# Western_Aero_2020.net
KiCad netlist of a schematic drawn in EAGLE
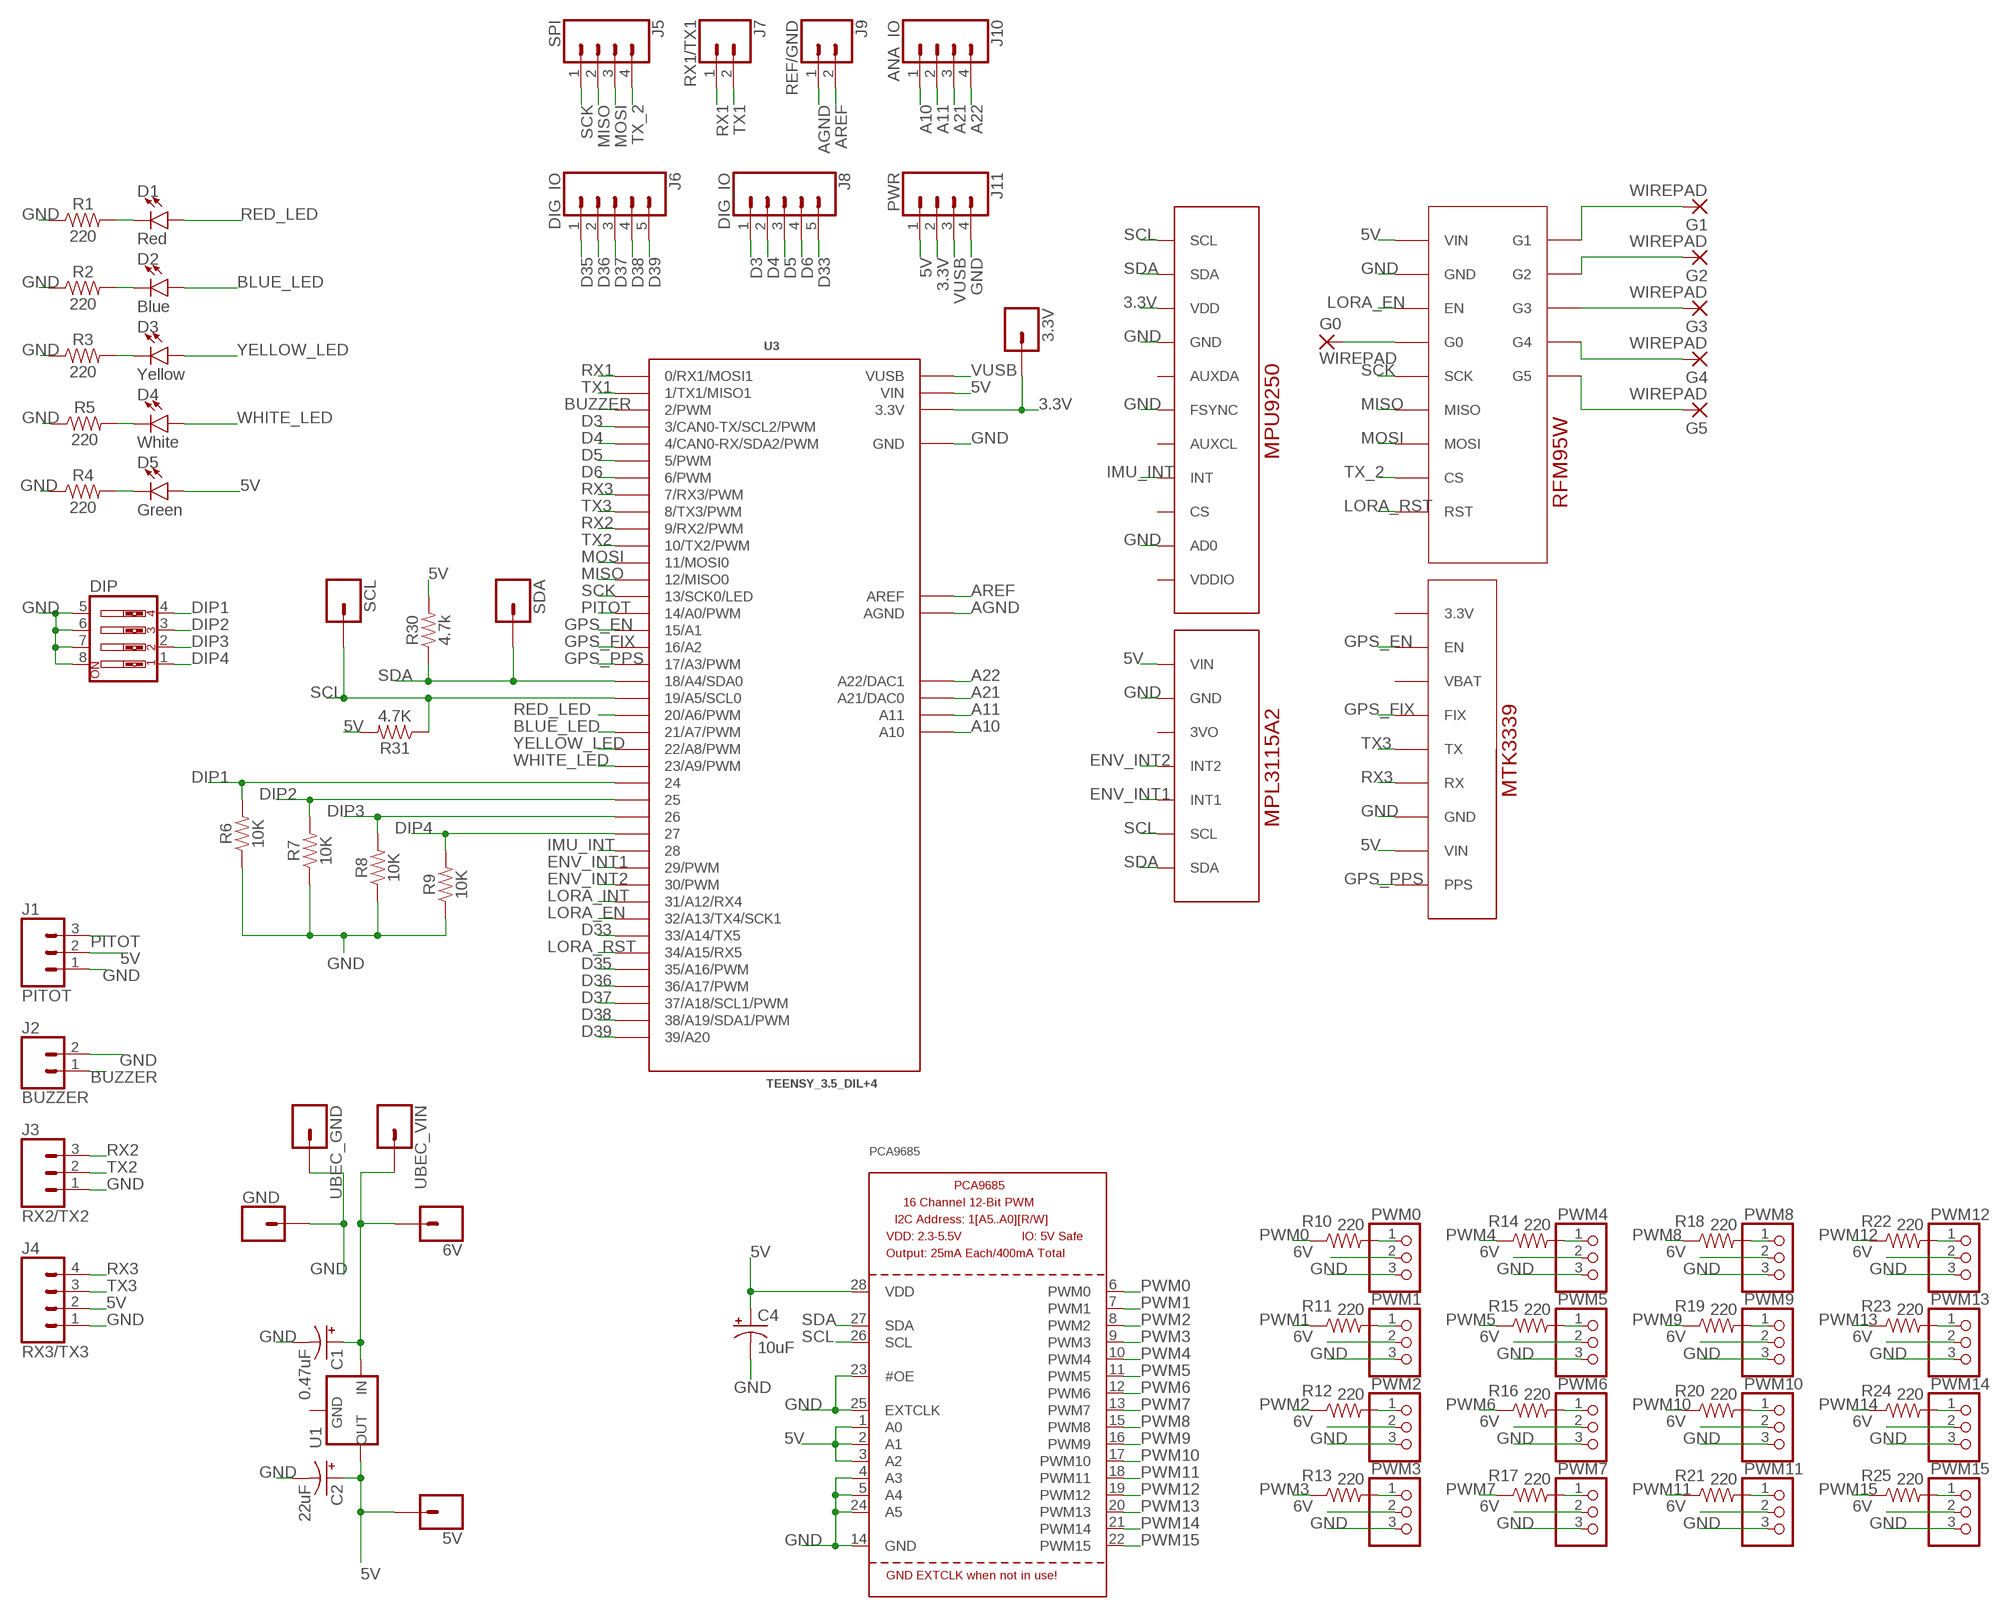
[diagram p0: schematic, sheet 1]

(export (version "E")
  (design (tool "Eeschema 10.0.6"))
  (components
    (comp (ref "3.3V")
      (value "CONN_01")
      (footprint "eagle-import:1X01")
      (libsource (lib "eagle-import") (part "CONN_01"))
    )
    (comp (ref "5V")
      (value "CONN_01")
      (footprint "eagle-import:1X01")
      (libsource (lib "eagle-import") (part "CONN_01"))
    )
    (comp (ref "6V")
      (value "CONN_01")
      (footprint "eagle-import:1X01")
      (libsource (lib "eagle-import") (part "CONN_01"))
    )
    (comp (ref "C1")
      (value "0.47uF")
      (footprint "eagle-import:CPOL-RADIAL-2.5MM-5MM")
      (libsource (lib "eagle-import") (part "10UF-POLAR-RADIAL-2.5MM-25V-20%"))
    )
    (comp (ref "C2")
      (value "22uF")
      (footprint "eagle-import:CPOL-RADIAL-2.5MM-5MM")
      (libsource (lib "eagle-import") (part "10UF-POLAR-RADIAL-2.5MM-25V-20%"))
    )
    (comp (ref "C4")
      (value "10uF")
      (footprint "eagle-import:CPOL-RADIAL-2.5MM-5MM")
      (libsource (lib "eagle-import") (part "10UF-POLAR-RADIAL-2.5MM-25V-20%"))
    )
    (comp (ref "D1")
      (value "Red")
      (footprint "eagle-import:LED_3MM")
      (libsource (lib "eagle-import") (part "LED3MM"))
    )
    (comp (ref "D2")
      (value "Blue")
      (footprint "eagle-import:LED_3MM")
      (libsource (lib "eagle-import") (part "LED3MM"))
    )
    (comp (ref "D3")
      (value "Yellow")
      (footprint "eagle-import:LED_3MM")
      (libsource (lib "eagle-import") (part "LED3MM"))
    )
    (comp (ref "D4")
      (value "White")
      (footprint "eagle-import:LED_3MM")
      (libsource (lib "eagle-import") (part "LED3MM"))
    )
    (comp (ref "D5")
      (value "Green")
      (footprint "eagle-import:LED_3MM")
      (libsource (lib "eagle-import") (part "LED3MM"))
    )
    (comp (ref "DIP")
      (value "SW_DIP-4")
      (footprint "eagle-import:EDG-04")
      (libsource (lib "eagle-import") (part "SW_DIP-4"))
    )
    (comp (ref "G0")
      (value "WIREPAD")
      (footprint "eagle-import:2,15_1,0")
      (libsource (lib "eagle-import") (part "WIREPAD2,15/1,0"))
    )
    (comp (ref "G1")
      (value "WIREPAD")
      (footprint "eagle-import:2,15_1,0")
      (libsource (lib "eagle-import") (part "WIREPAD2,15/1,0"))
    )
    (comp (ref "G2")
      (value "WIREPAD")
      (footprint "eagle-import:2,15_1,0")
      (libsource (lib "eagle-import") (part "WIREPAD2,15/1,0"))
    )
    (comp (ref "G3")
      (value "WIREPAD")
      (footprint "eagle-import:2,15_1,0")
      (libsource (lib "eagle-import") (part "WIREPAD2,15/1,0"))
    )
    (comp (ref "G4")
      (value "WIREPAD")
      (footprint "eagle-import:2,15_1,0")
      (libsource (lib "eagle-import") (part "WIREPAD2,15/1,0"))
    )
    (comp (ref "G5")
      (value "WIREPAD")
      (footprint "eagle-import:2,15_1,0")
      (libsource (lib "eagle-import") (part "WIREPAD2,15/1,0"))
    )
    (comp (ref "GND")
      (value "CONN_01")
      (footprint "eagle-import:1X01")
      (libsource (lib "eagle-import") (part "CONN_01"))
    )
    (comp (ref "J1")
      (value "PITOT")
      (footprint "eagle-import:1X03")
      (libsource (lib "eagle-import") (part "CONN_03"))
    )
    (comp (ref "J2")
      (value "BUZZER")
      (footprint "eagle-import:1X02")
      (libsource (lib "eagle-import") (part "CONN_02"))
    )
    (comp (ref "J3")
      (value "RX2/TX2")
      (footprint "eagle-import:1X03")
      (libsource (lib "eagle-import") (part "CONN_03"))
    )
    (comp (ref "J4")
      (value "RX3/TX3")
      (footprint "eagle-import:1X04")
      (libsource (lib "eagle-import") (part "CONN_04"))
    )
    (comp (ref "J5")
      (value "SPI")
      (footprint "eagle-import:1X04")
      (libsource (lib "eagle-import") (part "CONN_04"))
    )
    (comp (ref "J6")
      (value "DIG_IO")
      (footprint "eagle-import:1X05")
      (libsource (lib "eagle-import") (part "CONN_05"))
    )
    (comp (ref "J7")
      (value "RX1/TX1")
      (footprint "eagle-import:1X02")
      (libsource (lib "eagle-import") (part "CONN_02"))
    )
    (comp (ref "J8")
      (value "DIG_IO")
      (footprint "eagle-import:1X05")
      (libsource (lib "eagle-import") (part "CONN_05"))
    )
    (comp (ref "J9")
      (value "REF/GND")
      (footprint "eagle-import:1X02")
      (libsource (lib "eagle-import") (part "CONN_02"))
    )
    (comp (ref "J10")
      (value "ANA_IO")
      (footprint "eagle-import:1X04")
      (libsource (lib "eagle-import") (part "CONN_04"))
    )
    (comp (ref "J11")
      (value "PWR")
      (footprint "eagle-import:1X04")
      (libsource (lib "eagle-import") (part "CONN_04"))
    )
    (comp (ref "JP1")
      (value "PWM0")
      (footprint "eagle-import:1X03")
      (libsource (lib "eagle-import") (part "PINHD-1X3"))
    )
    (comp (ref "JP2")
      (value "PWM1")
      (footprint "eagle-import:1X03")
      (libsource (lib "eagle-import") (part "PINHD-1X3"))
    )
    (comp (ref "JP3")
      (value "PWM2")
      (footprint "eagle-import:1X03")
      (libsource (lib "eagle-import") (part "PINHD-1X3"))
    )
    (comp (ref "JP4")
      (value "PWM3")
      (footprint "eagle-import:1X03")
      (libsource (lib "eagle-import") (part "PINHD-1X3"))
    )
    (comp (ref "JP5")
      (value "PWM4")
      (footprint "eagle-import:1X03")
      (libsource (lib "eagle-import") (part "PINHD-1X3"))
    )
    (comp (ref "JP6")
      (value "PWM5")
      (footprint "eagle-import:1X03")
      (libsource (lib "eagle-import") (part "PINHD-1X3"))
    )
    (comp (ref "JP7")
      (value "PWM6")
      (footprint "eagle-import:1X03")
      (libsource (lib "eagle-import") (part "PINHD-1X3"))
    )
    (comp (ref "JP8")
      (value "PWM7")
      (footprint "eagle-import:1X03")
      (libsource (lib "eagle-import") (part "PINHD-1X3"))
    )
    (comp (ref "JP9")
      (value "PWM8")
      (footprint "eagle-import:1X03")
      (libsource (lib "eagle-import") (part "PINHD-1X3"))
    )
    (comp (ref "JP10")
      (value "PWM9")
      (footprint "eagle-import:1X03")
      (libsource (lib "eagle-import") (part "PINHD-1X3"))
    )
    (comp (ref "JP11")
      (value "PWM10")
      (footprint "eagle-import:1X03")
      (libsource (lib "eagle-import") (part "PINHD-1X3"))
    )
    (comp (ref "JP12")
      (value "PWM11")
      (footprint "eagle-import:1X03")
      (libsource (lib "eagle-import") (part "PINHD-1X3"))
    )
    (comp (ref "JP13")
      (value "PWM12")
      (footprint "eagle-import:1X03")
      (libsource (lib "eagle-import") (part "PINHD-1X3"))
    )
    (comp (ref "JP14")
      (value "PWM13")
      (footprint "eagle-import:1X03")
      (libsource (lib "eagle-import") (part "PINHD-1X3"))
    )
    (comp (ref "JP15")
      (value "PWM14")
      (footprint "eagle-import:1X03")
      (libsource (lib "eagle-import") (part "PINHD-1X3"))
    )
    (comp (ref "JP16")
      (value "PWM15")
      (footprint "eagle-import:1X03")
      (libsource (lib "eagle-import") (part "PINHD-1X3"))
    )
    (comp (ref "PCA9685")
      (value "PCA9685")
      (footprint "eagle-import:TSSOP28")
      (libsource (lib "eagle-import") (part "PCA9685"))
    )
    (comp (ref "R1")
      (value "220")
      (footprint "eagle-import:AXIAL-0.3")
      (libsource (lib "eagle-import") (part "330OHM-HORIZ-1/10W-5%"))
    )
    (comp (ref "R2")
      (value "220")
      (footprint "eagle-import:AXIAL-0.3")
      (libsource (lib "eagle-import") (part "330OHM-HORIZ-1/10W-5%"))
    )
    (comp (ref "R3")
      (value "220")
      (footprint "eagle-import:AXIAL-0.3")
      (libsource (lib "eagle-import") (part "330OHM-HORIZ-1/10W-5%"))
    )
    (comp (ref "R4")
      (value "220")
      (footprint "eagle-import:AXIAL-0.3")
      (libsource (lib "eagle-import") (part "330OHM-HORIZ-1/10W-5%"))
    )
    (comp (ref "R5")
      (value "220")
      (footprint "eagle-import:AXIAL-0.3")
      (libsource (lib "eagle-import") (part "330OHM-HORIZ-1/10W-5%"))
    )
    (comp (ref "R6")
      (value "10K")
      (footprint "eagle-import:AXIAL-0.3")
      (libsource (lib "eagle-import") (part "330OHM-HORIZ-1/10W-5%"))
    )
    (comp (ref "R7")
      (value "10K")
      (footprint "eagle-import:AXIAL-0.3")
      (libsource (lib "eagle-import") (part "330OHM-HORIZ-1/10W-5%"))
    )
    (comp (ref "R8")
      (value "10K")
      (footprint "eagle-import:AXIAL-0.3")
      (libsource (lib "eagle-import") (part "330OHM-HORIZ-1/10W-5%"))
    )
    (comp (ref "R9")
      (value "10K")
      (footprint "eagle-import:AXIAL-0.3")
      (libsource (lib "eagle-import") (part "330OHM-HORIZ-1/10W-5%"))
    )
    (comp (ref "R10")
      (value "220")
      (footprint "eagle-import:AXIAL-0.3")
      (libsource (lib "eagle-import") (part "330OHM-HORIZ-1/10W-5%"))
    )
    (comp (ref "R11")
      (value "220")
      (footprint "eagle-import:AXIAL-0.3")
      (libsource (lib "eagle-import") (part "330OHM-HORIZ-1/10W-5%"))
    )
    (comp (ref "R12")
      (value "220")
      (footprint "eagle-import:AXIAL-0.3")
      (libsource (lib "eagle-import") (part "330OHM-HORIZ-1/10W-5%"))
    )
    (comp (ref "R13")
      (value "220")
      (footprint "eagle-import:AXIAL-0.3")
      (libsource (lib "eagle-import") (part "330OHM-HORIZ-1/10W-5%"))
    )
    (comp (ref "R14")
      (value "220")
      (footprint "eagle-import:AXIAL-0.3")
      (libsource (lib "eagle-import") (part "330OHM-HORIZ-1/10W-5%"))
    )
    (comp (ref "R15")
      (value "220")
      (footprint "eagle-import:AXIAL-0.3")
      (libsource (lib "eagle-import") (part "330OHM-HORIZ-1/10W-5%"))
    )
    (comp (ref "R16")
      (value "220")
      (footprint "eagle-import:AXIAL-0.3")
      (libsource (lib "eagle-import") (part "330OHM-HORIZ-1/10W-5%"))
    )
    (comp (ref "R17")
      (value "220")
      (footprint "eagle-import:AXIAL-0.3")
      (libsource (lib "eagle-import") (part "330OHM-HORIZ-1/10W-5%"))
    )
    (comp (ref "R18")
      (value "220")
      (footprint "eagle-import:AXIAL-0.3")
      (libsource (lib "eagle-import") (part "330OHM-HORIZ-1/10W-5%"))
    )
    (comp (ref "R19")
      (value "220")
      (footprint "eagle-import:AXIAL-0.3")
      (libsource (lib "eagle-import") (part "330OHM-HORIZ-1/10W-5%"))
    )
    (comp (ref "R20")
      (value "220")
      (footprint "eagle-import:AXIAL-0.3")
      (libsource (lib "eagle-import") (part "330OHM-HORIZ-1/10W-5%"))
    )
    (comp (ref "R21")
      (value "220")
      (footprint "eagle-import:AXIAL-0.3")
      (libsource (lib "eagle-import") (part "330OHM-HORIZ-1/10W-5%"))
    )
    (comp (ref "R22")
      (value "220")
      (footprint "eagle-import:AXIAL-0.3")
      (libsource (lib "eagle-import") (part "330OHM-HORIZ-1/10W-5%"))
    )
    (comp (ref "R23")
      (value "220")
      (footprint "eagle-import:AXIAL-0.3")
      (libsource (lib "eagle-import") (part "330OHM-HORIZ-1/10W-5%"))
    )
    (comp (ref "R24")
      (value "220")
      (footprint "eagle-import:AXIAL-0.3")
      (libsource (lib "eagle-import") (part "330OHM-HORIZ-1/10W-5%"))
    )
    (comp (ref "R25")
      (value "220")
      (footprint "eagle-import:AXIAL-0.3")
      (libsource (lib "eagle-import") (part "330OHM-HORIZ-1/10W-5%"))
    )
    (comp (ref "R30")
      (value "4.7k")
      (footprint "eagle-import:AXIAL-0.3")
      (libsource (lib "eagle-import") (part "330OHM-HORIZ-1/10W-5%"))
    )
    (comp (ref "R31")
      (value "4.7K")
      (footprint "eagle-import:AXIAL-0.3")
      (libsource (lib "eagle-import") (part "330OHM-HORIZ-1/10W-5%"))
    )
    (comp (ref "SCL")
      (value "CONN_01")
      (footprint "eagle-import:1X01")
      (libsource (lib "eagle-import") (part "CONN_01"))
    )
    (comp (ref "SDA")
      (value "CONN_01")
      (footprint "eagle-import:1X01")
      (libsource (lib "eagle-import") (part "CONN_01"))
    )
    (comp (ref "U1")
      (value "V_REG_78XXSINK")
      (footprint "eagle-import:TO220-IGO")
      (libsource (lib "eagle-import") (part "V_REG_78XXSINK"))
    )
    (comp (ref "U3")
      (value "TEENSY_3.5_DIL+4")
      (footprint "eagle-import:TEENSY_3.5_DIL+4")
      (libsource (lib "eagle-import") (part "TEENSY_3.5_DIL+4"))
    )
    (comp (ref "U5")
      (value "SPARKFUN_MPU9250_IMU")
      (footprint "eagle-import:SPARKFUN_MPU9250_IMU")
      (libsource (lib "eagle-import") (part "SPARKFUN_MPU9250_IMU"))
    )
    (comp (ref "U6")
      (value "ADAFRUIT_MPL3115A2_BAROMETER")
      (footprint "eagle-import:ADAFRUIT_MPL3115A2_BAROMETER")
      (libsource (lib "eagle-import") (part "ADAFRUIT_MPL3115A2_BAROMETER"))
    )
    (comp (ref "U8")
      (value "ADAFRUIT_RFM95W_LORA_RADIO")
      (footprint "eagle-import:ADAFRUIT_RFM95W_LORA_RADIO")
      (libsource (lib "eagle-import") (part "ADAFRUIT_RFM95W_LORA_RADIO"))
    )
    (comp (ref "U9")
      (value "ADAFRUIT_MTK3339_GPS")
      (footprint "eagle-import:ADAFRUIT_MTK3339_GPS")
      (libsource (lib "eagle-import") (part "ADAFRUIT_MTK3339_GPS"))
    )
    (comp (ref "UBEC_GND")
      (value "CONN_01")
      (footprint "eagle-import:1X01")
      (libsource (lib "eagle-import") (part "CONN_01"))
    )
    (comp (ref "UBEC_VIN")
      (value "CONN_01")
      (footprint "eagle-import:1X01")
      (libsource (lib "eagle-import") (part "CONN_01"))
    )
  )
  (nets
    (net (code "1") (name "/3.3V") (class "Default")
      (node (ref "3.3V") (pin "1") (pinfunction "1_1") (pintype "passive"))
      (node (ref "J11") (pin "2") (pinfunction "2_2") (pintype "passive"))
      (node (ref "U3") (pin "3.3V") (pinfunction "3.3V_3.3V") (pintype "power_in"))
      (node (ref "U3") (pin "3.3V3") (pinfunction "3.3V_3.3V3") (pintype "power_in"))
      (node (ref "U5") (pin "VDD") (pinfunction "VDD_VDD") (pintype "bidirectional"))
    )
    (net (code "2") (name "/5V") (class "Default")
      (node (ref "5V") (pin "1") (pinfunction "1_1") (pintype "passive"))
      (node (ref "C2") (pin "1") (pinfunction "+_1") (pintype "passive"))
      (node (ref "C4") (pin "1") (pinfunction "+_1") (pintype "passive"))
      (node (ref "D5") (pin "A") (pinfunction "A_A") (pintype "passive"))
      (node (ref "J1") (pin "2") (pinfunction "2_2") (pintype "passive"))
      (node (ref "J11") (pin "1") (pinfunction "1_1") (pintype "passive"))
      (node (ref "J4") (pin "2") (pinfunction "2_2") (pintype "passive"))
      (node (ref "PCA9685") (pin "1") (pinfunction "A0_1") (pintype "bidirectional"))
      (node (ref "PCA9685") (pin "2") (pinfunction "A1_2") (pintype "bidirectional"))
      (node (ref "PCA9685") (pin "28") (pinfunction "VDD_28") (pintype "power_in"))
      (node (ref "PCA9685") (pin "3") (pinfunction "A2_3") (pintype "bidirectional"))
      (node (ref "R30") (pin "P$2") (pinfunction "2_P$2") (pintype "passive"))
      (node (ref "R31") (pin "P$2") (pinfunction "2_P$2") (pintype "passive"))
      (node (ref "U1") (pin "OUT") (pinfunction "OUT_OUT") (pintype "passive"))
      (node (ref "U3") (pin "VIN") (pinfunction "VIN_VIN") (pintype "power_in"))
      (node (ref "U6") (pin "VIN") (pinfunction "VIN_VIN") (pintype "bidirectional"))
      (node (ref "U8") (pin "1") (pinfunction "VIN_1") (pintype "bidirectional"))
      (node (ref "U9") (pin "VIN") (pinfunction "VIN_VIN") (pintype "bidirectional"))
    )
    (net (code "3") (name "/6V") (class "Default")
      (node (ref "6V") (pin "1") (pinfunction "1_1") (pintype "passive"))
      (node (ref "C1") (pin "1") (pinfunction "+_1") (pintype "passive"))
      (node (ref "JP1") (pin "2") (pinfunction "2_2") (pintype "passive"))
      (node (ref "JP10") (pin "2") (pinfunction "2_2") (pintype "passive"))
      (node (ref "JP11") (pin "2") (pinfunction "2_2") (pintype "passive"))
      (node (ref "JP12") (pin "2") (pinfunction "2_2") (pintype "passive"))
      (node (ref "JP13") (pin "2") (pinfunction "2_2") (pintype "passive"))
      (node (ref "JP14") (pin "2") (pinfunction "2_2") (pintype "passive"))
      (node (ref "JP15") (pin "2") (pinfunction "2_2") (pintype "passive"))
      (node (ref "JP16") (pin "2") (pinfunction "2_2") (pintype "passive"))
      (node (ref "JP2") (pin "2") (pinfunction "2_2") (pintype "passive"))
      (node (ref "JP3") (pin "2") (pinfunction "2_2") (pintype "passive"))
      (node (ref "JP4") (pin "2") (pinfunction "2_2") (pintype "passive"))
      (node (ref "JP5") (pin "2") (pinfunction "2_2") (pintype "passive"))
      (node (ref "JP6") (pin "2") (pinfunction "2_2") (pintype "passive"))
      (node (ref "JP7") (pin "2") (pinfunction "2_2") (pintype "passive"))
      (node (ref "JP8") (pin "2") (pinfunction "2_2") (pintype "passive"))
      (node (ref "JP9") (pin "2") (pinfunction "2_2") (pintype "passive"))
      (node (ref "U1") (pin "IN") (pinfunction "IN_IN") (pintype "input"))
      (node (ref "UBEC_VIN") (pin "1") (pinfunction "1_1") (pintype "passive"))
    )
    (net (code "4") (name "/A10") (class "Default")
      (node (ref "J10") (pin "1") (pinfunction "1_1") (pintype "passive"))
      (node (ref "U3") (pin "A10") (pinfunction "A10_A10") (pintype "bidirectional"))
    )
    (net (code "5") (name "/A11") (class "Default")
      (node (ref "J10") (pin "2") (pinfunction "2_2") (pintype "passive"))
      (node (ref "U3") (pin "A11") (pinfunction "A11_A11") (pintype "bidirectional"))
    )
    (net (code "6") (name "/A21") (class "Default")
      (node (ref "J10") (pin "3") (pinfunction "3_3") (pintype "passive"))
      (node (ref "U3") (pin "A21") (pinfunction "A21/DAC0_A21") (pintype "bidirectional"))
    )
    (net (code "7") (name "/A22") (class "Default")
      (node (ref "J10") (pin "4") (pinfunction "4_4") (pintype "passive"))
      (node (ref "U3") (pin "A22") (pinfunction "A22/DAC1_A22") (pintype "bidirectional"))
    )
    (net (code "8") (name "/AGND") (class "Default")
      (node (ref "J9") (pin "1") (pinfunction "1_1") (pintype "passive"))
      (node (ref "U3") (pin "AGND") (pinfunction "AGND_AGND") (pintype "power_in"))
    )
    (net (code "9") (name "/AREF") (class "Default")
      (node (ref "J9") (pin "2") (pinfunction "2_2") (pintype "passive"))
      (node (ref "U3") (pin "AREF") (pinfunction "AREF_AREF") (pintype "power_in"))
    )
    (net (code "10") (name "/BLUE_LED") (class "Default")
      (node (ref "D2") (pin "A") (pinfunction "A_A") (pintype "passive"))
      (node (ref "U3") (pin "21/A7") (pinfunction "21/A7/PWM_21/A7") (pintype "bidirectional"))
    )
    (net (code "11") (name "/BUZZER") (class "Default")
      (node (ref "J2") (pin "1") (pinfunction "1_1") (pintype "passive"))
      (node (ref "U3") (pin "2") (pinfunction "2/PWM_2") (pintype "bidirectional"))
    )
    (net (code "12") (name "/D3") (class "Default")
      (node (ref "J8") (pin "1") (pinfunction "1_1") (pintype "passive"))
      (node (ref "U3") (pin "3") (pinfunction "3/CAN0-TX/SCL2/PWM_3") (pintype "bidirectional"))
    )
    (net (code "13") (name "/D4") (class "Default")
      (node (ref "J8") (pin "2") (pinfunction "2_2") (pintype "passive"))
      (node (ref "U3") (pin "4") (pinfunction "4/CAN0-RX/SDA2/PWM_4") (pintype "bidirectional"))
    )
    (net (code "14") (name "/D5") (class "Default")
      (node (ref "J8") (pin "3") (pinfunction "3_3") (pintype "passive"))
      (node (ref "U3") (pin "5") (pinfunction "5/PWM_5") (pintype "bidirectional"))
    )
    (net (code "15") (name "/D6") (class "Default")
      (node (ref "J8") (pin "4") (pinfunction "4_4") (pintype "passive"))
      (node (ref "U3") (pin "6") (pinfunction "6/PWM_6") (pintype "bidirectional"))
    )
    (net (code "16") (name "/D33") (class "Default")
      (node (ref "J8") (pin "5") (pinfunction "5_5") (pintype "passive"))
      (node (ref "U3") (pin "33/A14") (pinfunction "33/A14/TX5_33/A14") (pintype "bidirectional"))
    )
    (net (code "17") (name "/D35") (class "Default")
      (node (ref "J6") (pin "1") (pinfunction "1_1") (pintype "passive"))
      (node (ref "U3") (pin "35/A16") (pinfunction "35/A16/PWM_35/A16") (pintype "bidirectional"))
    )
    (net (code "18") (name "/D36") (class "Default")
      (node (ref "J6") (pin "2") (pinfunction "2_2") (pintype "passive"))
      (node (ref "U3") (pin "36/A17") (pinfunction "36/A17/PWM_36/A17") (pintype "bidirectional"))
    )
    (net (code "19") (name "/D37") (class "Default")
      (node (ref "J6") (pin "3") (pinfunction "3_3") (pintype "passive"))
      (node (ref "U3") (pin "37/A18") (pinfunction "37/A18/SCL1/PWM_37/A18") (pintype "bidirectional"))
    )
    (net (code "20") (name "/D38") (class "Default")
      (node (ref "J6") (pin "4") (pinfunction "4_4") (pintype "passive"))
      (node (ref "U3") (pin "38/A19") (pinfunction "38/A19/SDA1/PWM_38/A19") (pintype "bidirectional"))
    )
    (net (code "21") (name "/D39") (class "Default")
      (node (ref "J6") (pin "5") (pinfunction "5_5") (pintype "passive"))
      (node (ref "U3") (pin "39/A20") (pinfunction "39/A20_39/A20") (pintype "bidirectional"))
    )
    (net (code "22") (name "/DIP1") (class "Default")
      (node (ref "DIP") (pin "4") (pinfunction "4_4") (pintype "passive"))
      (node (ref "R6") (pin "P$2") (pinfunction "2_P$2") (pintype "passive"))
      (node (ref "U3") (pin "24") (pinfunction "24_24") (pintype "bidirectional"))
    )
    (net (code "23") (name "/DIP2") (class "Default")
      (node (ref "DIP") (pin "3") (pinfunction "3_3") (pintype "passive"))
      (node (ref "R7") (pin "P$2") (pinfunction "2_P$2") (pintype "passive"))
      (node (ref "U3") (pin "25") (pinfunction "25_25") (pintype "bidirectional"))
    )
    (net (code "24") (name "/DIP3") (class "Default")
      (node (ref "DIP") (pin "2") (pinfunction "2_2") (pintype "passive"))
      (node (ref "R8") (pin "P$2") (pinfunction "2_P$2") (pintype "passive"))
      (node (ref "U3") (pin "26") (pinfunction "26_26") (pintype "bidirectional"))
    )
    (net (code "25") (name "/DIP4") (class "Default")
      (node (ref "DIP") (pin "1") (pinfunction "1_1") (pintype "passive"))
      (node (ref "R9") (pin "P$2") (pinfunction "2_P$2") (pintype "passive"))
      (node (ref "U3") (pin "27") (pinfunction "27_27") (pintype "bidirectional"))
    )
    (net (code "26") (name "/ENV_INT1") (class "Default")
      (node (ref "U3") (pin "29") (pinfunction "29/PWM_29") (pintype "bidirectional"))
      (node (ref "U6") (pin "INT1") (pinfunction "INT1_INT1") (pintype "bidirectional"))
    )
    (net (code "27") (name "/ENV_INT2") (class "Default")
      (node (ref "U3") (pin "30") (pinfunction "30/PWM_30") (pintype "bidirectional"))
      (node (ref "U6") (pin "INT2") (pinfunction "INT2_INT2") (pintype "bidirectional"))
    )
    (net (code "28") (name "/GND") (class "Default")
      (node (ref "C1") (pin "2") (pinfunction "-_2") (pintype "passive"))
      (node (ref "C2") (pin "2") (pinfunction "-_2") (pintype "passive"))
      (node (ref "C4") (pin "2") (pinfunction "-_2") (pintype "passive"))
      (node (ref "DIP") (pin "5") (pinfunction "5_5") (pintype "passive"))
      (node (ref "DIP") (pin "6") (pinfunction "6_6") (pintype "passive"))
      (node (ref "DIP") (pin "7") (pinfunction "7_7") (pintype "passive"))
      (node (ref "DIP") (pin "8") (pinfunction "8_8") (pintype "passive"))
      (node (ref "GND") (pin "1") (pinfunction "1_1") (pintype "passive"))
      (node (ref "J1") (pin "1") (pinfunction "1_1") (pintype "passive"))
      (node (ref "J11") (pin "4") (pinfunction "4_4") (pintype "passive"))
      (node (ref "J2") (pin "2") (pinfunction "2_2") (pintype "passive"))
      (node (ref "J3") (pin "1") (pinfunction "1_1") (pintype "passive"))
      (node (ref "J4") (pin "1") (pinfunction "1_1") (pintype "passive"))
      (node (ref "JP1") (pin "3") (pinfunction "3_3") (pintype "passive"))
      (node (ref "JP10") (pin "3") (pinfunction "3_3") (pintype "passive"))
      (node (ref "JP11") (pin "3") (pinfunction "3_3") (pintype "passive"))
      (node (ref "JP12") (pin "3") (pinfunction "3_3") (pintype "passive"))
      (node (ref "JP13") (pin "3") (pinfunction "3_3") (pintype "passive"))
      (node (ref "JP14") (pin "3") (pinfunction "3_3") (pintype "passive"))
      (node (ref "JP15") (pin "3") (pinfunction "3_3") (pintype "passive"))
      (node (ref "JP16") (pin "3") (pinfunction "3_3") (pintype "passive"))
      (node (ref "JP2") (pin "3") (pinfunction "3_3") (pintype "passive"))
      (node (ref "JP3") (pin "3") (pinfunction "3_3") (pintype "passive"))
      (node (ref "JP4") (pin "3") (pinfunction "3_3") (pintype "passive"))
      (node (ref "JP5") (pin "3") (pinfunction "3_3") (pintype "passive"))
      (node (ref "JP6") (pin "3") (pinfunction "3_3") (pintype "passive"))
      (node (ref "JP7") (pin "3") (pinfunction "3_3") (pintype "passive"))
      (node (ref "JP8") (pin "3") (pinfunction "3_3") (pintype "passive"))
      (node (ref "JP9") (pin "3") (pinfunction "3_3") (pintype "passive"))
      (node (ref "PCA9685") (pin "14") (pinfunction "GND_14") (pintype "power_in"))
      (node (ref "PCA9685") (pin "23") (pinfunction "#OE_23") (pintype "input"))
      (node (ref "PCA9685") (pin "24") (pinfunction "A5_24") (pintype "bidirectional"))
      (node (ref "PCA9685") (pin "25") (pinfunction "EXTCLK_25") (pintype "input"))
      (node (ref "PCA9685") (pin "4") (pinfunction "A3_4") (pintype "bidirectional"))
      (node (ref "PCA9685") (pin "5") (pinfunction "A4_5") (pintype "bidirectional"))
      (node (ref "R1") (pin "P$1") (pinfunction "1_P$1") (pintype "passive"))
      (node (ref "R2") (pin "P$1") (pinfunction "1_P$1") (pintype "passive"))
      (node (ref "R3") (pin "P$1") (pinfunction "1_P$1") (pintype "passive"))
      (node (ref "R4") (pin "P$1") (pinfunction "1_P$1") (pintype "passive"))
      (node (ref "R5") (pin "P$1") (pinfunction "1_P$1") (pintype "passive"))
      (node (ref "R6") (pin "P$1") (pinfunction "1_P$1") (pintype "passive"))
      (node (ref "R7") (pin "P$1") (pinfunction "1_P$1") (pintype "passive"))
      (node (ref "R8") (pin "P$1") (pinfunction "1_P$1") (pintype "passive"))
      (node (ref "R9") (pin "P$1") (pinfunction "1_P$1") (pintype "passive"))
      (node (ref "U3") (pin "GND") (pinfunction "GND_GND") (pintype "power_in"))
      (node (ref "U3") (pin "GND1") (pinfunction "GND_GND1") (pintype "power_in"))
      (node (ref "U5") (pin "AD0") (pinfunction "AD0_AD0") (pintype "bidirectional"))
      (node (ref "U5") (pin "FSYNC") (pinfunction "FSYNC_FSYNC") (pintype "bidirectional"))
      (node (ref "U5") (pin "GND") (pinfunction "GND_GND") (pintype "bidirectional"))
      (node (ref "U6") (pin "GND") (pinfunction "GND_GND") (pintype "bidirectional"))
      (node (ref "U8") (pin "2") (pinfunction "GND_2") (pintype "bidirectional"))
      (node (ref "U9") (pin "GND") (pinfunction "GND_GND") (pintype "bidirectional"))
      (node (ref "UBEC_GND") (pin "1") (pinfunction "1_1") (pintype "passive"))
    )
    (net (code "29") (name "/GPS_EN") (class "Default")
      (node (ref "U3") (pin "15/A1") (pinfunction "15/A1_15/A1") (pintype "bidirectional"))
      (node (ref "U9") (pin "EN") (pinfunction "EN_EN") (pintype "bidirectional"))
    )
    (net (code "30") (name "/GPS_FIX") (class "Default")
      (node (ref "U3") (pin "16/A2") (pinfunction "16/A2_16/A2") (pintype "bidirectional"))
      (node (ref "U9") (pin "FIX") (pinfunction "FIX_FIX") (pintype "bidirectional"))
    )
    (net (code "31") (name "/GPS_PPS") (class "Default")
      (node (ref "U3") (pin "17/A3") (pinfunction "17/A3/PWM_17/A3") (pintype "bidirectional"))
      (node (ref "U9") (pin "PPS") (pinfunction "PPS_PPS") (pintype "bidirectional"))
    )
    (net (code "32") (name "/IMU_INT") (class "Default")
      (node (ref "U3") (pin "28") (pinfunction "28_28") (pintype "bidirectional"))
      (node (ref "U5") (pin "INT") (pinfunction "INT_INT") (pintype "bidirectional"))
    )
    (net (code "33") (name "/LORA_EN") (class "Default")
      (node (ref "U3") (pin "32/A13") (pinfunction "32/A13/TX4/SCK1_32/A13") (pintype "bidirectional"))
      (node (ref "U8") (pin "3") (pinfunction "EN_3") (pintype "bidirectional"))
    )
    (net (code "34") (name "/LORA_INT") (class "Default")
      (node (ref "U3") (pin "31/A12") (pinfunction "31/A12/RX4_31/A12") (pintype "bidirectional"))
    )
    (net (code "35") (name "/LORA_RST") (class "Default")
      (node (ref "U3") (pin "34/A15") (pinfunction "34/A15/RX5_34/A15") (pintype "bidirectional"))
      (node (ref "U8") (pin "9") (pinfunction "RST_9") (pintype "bidirectional"))
    )
    (net (code "36") (name "/MISO") (class "Default")
      (node (ref "J5") (pin "2") (pinfunction "2_2") (pintype "passive"))
      (node (ref "U3") (pin "12") (pinfunction "12/MISO0_12") (pintype "bidirectional"))
      (node (ref "U8") (pin "6") (pinfunction "MISO_6") (pintype "bidirectional"))
    )
    (net (code "37") (name "/MOSI") (class "Default")
      (node (ref "J5") (pin "3") (pinfunction "3_3") (pintype "passive"))
      (node (ref "U3") (pin "11") (pinfunction "11/MOSI0_11") (pintype "bidirectional"))
      (node (ref "U8") (pin "7") (pinfunction "MOSI_7") (pintype "bidirectional"))
    )
    (net (code "38") (name "/PITOT") (class "Default")
      (node (ref "J1") (pin "3") (pinfunction "3_3") (pintype "passive"))
      (node (ref "U3") (pin "14/A0") (pinfunction "14/A0/PWM_14/A0") (pintype "bidirectional"))
    )
    (net (code "39") (name "/PWM0") (class "Default")
      (node (ref "PCA9685") (pin "6") (pinfunction "PWM0_6") (pintype "output"))
      (node (ref "R10") (pin "P$1") (pinfunction "1_P$1") (pintype "passive"))
    )
    (net (code "40") (name "/PWM1") (class "Default")
      (node (ref "PCA9685") (pin "7") (pinfunction "PWM1_7") (pintype "output"))
      (node (ref "R11") (pin "P$1") (pinfunction "1_P$1") (pintype "passive"))
    )
    (net (code "41") (name "/PWM2") (class "Default")
      (node (ref "PCA9685") (pin "8") (pinfunction "PWM2_8") (pintype "output"))
      (node (ref "R12") (pin "P$1") (pinfunction "1_P$1") (pintype "passive"))
    )
    (net (code "42") (name "/PWM3") (class "Default")
      (node (ref "PCA9685") (pin "9") (pinfunction "PWM3_9") (pintype "output"))
      (node (ref "R13") (pin "P$1") (pinfunction "1_P$1") (pintype "passive"))
    )
    (net (code "43") (name "/PWM4") (class "Default")
      (node (ref "PCA9685") (pin "10") (pinfunction "PWM4_10") (pintype "output"))
      (node (ref "R14") (pin "P$1") (pinfunction "1_P$1") (pintype "passive"))
    )
    (net (code "44") (name "/PWM5") (class "Default")
      (node (ref "PCA9685") (pin "11") (pinfunction "PWM5_11") (pintype "output"))
      (node (ref "R15") (pin "P$1") (pinfunction "1_P$1") (pintype "passive"))
    )
    (net (code "45") (name "/PWM6") (class "Default")
      (node (ref "PCA9685") (pin "12") (pinfunction "PWM6_12") (pintype "output"))
      (node (ref "R16") (pin "P$1") (pinfunction "1_P$1") (pintype "passive"))
    )
    (net (code "46") (name "/PWM7") (class "Default")
      (node (ref "PCA9685") (pin "13") (pinfunction "PWM7_13") (pintype "output"))
      (node (ref "R17") (pin "P$1") (pinfunction "1_P$1") (pintype "passive"))
    )
    (net (code "47") (name "/PWM8") (class "Default")
      (node (ref "PCA9685") (pin "15") (pinfunction "PWM8_15") (pintype "output"))
      (node (ref "R18") (pin "P$1") (pinfunction "1_P$1") (pintype "passive"))
    )
    (net (code "48") (name "/PWM9") (class "Default")
      (node (ref "PCA9685") (pin "16") (pinfunction "PWM9_16") (pintype "output"))
      (node (ref "R19") (pin "P$1") (pinfunction "1_P$1") (pintype "passive"))
    )
    (net (code "49") (name "/PWM10") (class "Default")
      (node (ref "PCA9685") (pin "17") (pinfunction "PWM10_17") (pintype "output"))
      (node (ref "R20") (pin "P$1") (pinfunction "1_P$1") (pintype "passive"))
    )
    (net (code "50") (name "/PWM11") (class "Default")
      (node (ref "PCA9685") (pin "18") (pinfunction "PWM11_18") (pintype "output"))
      (node (ref "R21") (pin "P$1") (pinfunction "1_P$1") (pintype "passive"))
    )
    (net (code "51") (name "/PWM12") (class "Default")
      (node (ref "PCA9685") (pin "19") (pinfunction "PWM12_19") (pintype "output"))
      (node (ref "R22") (pin "P$1") (pinfunction "1_P$1") (pintype "passive"))
    )
    (net (code "52") (name "/PWM13") (class "Default")
      (node (ref "PCA9685") (pin "20") (pinfunction "PWM13_20") (pintype "output"))
      (node (ref "R23") (pin "P$1") (pinfunction "1_P$1") (pintype "passive"))
    )
    (net (code "53") (name "/PWM14") (class "Default")
      (node (ref "PCA9685") (pin "21") (pinfunction "PWM14_21") (pintype "output"))
      (node (ref "R24") (pin "P$1") (pinfunction "1_P$1") (pintype "passive"))
    )
    (net (code "54") (name "/PWM15") (class "Default")
      (node (ref "PCA9685") (pin "22") (pinfunction "PWM15_22") (pintype "output"))
      (node (ref "R25") (pin "P$1") (pinfunction "1_P$1") (pintype "passive"))
    )
    (net (code "55") (name "/RED_LED") (class "Default")
      (node (ref "D1") (pin "A") (pinfunction "A_A") (pintype "passive"))
      (node (ref "U3") (pin "20/A6") (pinfunction "20/A6/PWM_20/A6") (pintype "bidirectional"))
    )
    (net (code "56") (name "/RX1") (class "Default")
      (node (ref "J7") (pin "1") (pinfunction "1_1") (pintype "passive"))
      (node (ref "U3") (pin "0") (pinfunction "0/RX1/MOSI1_0") (pintype "bidirectional"))
    )
    (net (code "57") (name "/RX2") (class "Default")
      (node (ref "J3") (pin "3") (pinfunction "3_3") (pintype "passive"))
      (node (ref "U3") (pin "9") (pinfunction "9/RX2/PWM_9") (pintype "bidirectional"))
    )
    (net (code "58") (name "/RX3") (class "Default")
      (node (ref "J4") (pin "4") (pinfunction "4_4") (pintype "passive"))
      (node (ref "U3") (pin "7") (pinfunction "7/RX3/PWM_7") (pintype "bidirectional"))
      (node (ref "U9") (pin "RX") (pinfunction "RX_RX") (pintype "bidirectional"))
    )
    (net (code "59") (name "/SCK") (class "Default")
      (node (ref "J5") (pin "1") (pinfunction "1_1") (pintype "passive"))
      (node (ref "U3") (pin "13") (pinfunction "13/SCK0/LED_13") (pintype "bidirectional"))
      (node (ref "U8") (pin "5") (pinfunction "SCK_5") (pintype "bidirectional"))
    )
    (net (code "60") (name "/SCL") (class "Default")
      (node (ref "PCA9685") (pin "26") (pinfunction "SCL_26") (pintype "bidirectional"))
      (node (ref "R31") (pin "P$1") (pinfunction "1_P$1") (pintype "passive"))
      (node (ref "SCL") (pin "1") (pinfunction "1_1") (pintype "passive"))
      (node (ref "U3") (pin "19/A5") (pinfunction "19/A5/SCL0_19/A5") (pintype "bidirectional"))
      (node (ref "U5") (pin "SCL") (pinfunction "SCL_SCL") (pintype "bidirectional"))
      (node (ref "U6") (pin "SCL") (pinfunction "SCL_SCL") (pintype "bidirectional"))
    )
    (net (code "61") (name "/SDA") (class "Default")
      (node (ref "PCA9685") (pin "27") (pinfunction "SDA_27") (pintype "bidirectional"))
      (node (ref "R30") (pin "P$1") (pinfunction "1_P$1") (pintype "passive"))
      (node (ref "SDA") (pin "1") (pinfunction "1_1") (pintype "passive"))
      (node (ref "U3") (pin "18/A4") (pinfunction "18/A4/SDA0_18/A4") (pintype "bidirectional"))
      (node (ref "U5") (pin "SDA") (pinfunction "SDA_SDA") (pintype "bidirectional"))
      (node (ref "U6") (pin "SDA") (pinfunction "SDA_SDA") (pintype "bidirectional"))
    )
    (net (code "62") (name "/TX1") (class "Default")
      (node (ref "J7") (pin "2") (pinfunction "2_2") (pintype "passive"))
      (node (ref "U3") (pin "1") (pinfunction "1/TX1/MISO1_1") (pintype "bidirectional"))
    )
    (net (code "63") (name "/TX2") (class "Default")
      (node (ref "J3") (pin "2") (pinfunction "2_2") (pintype "passive"))
      (node (ref "U3") (pin "10") (pinfunction "10/TX2/PWM_10") (pintype "bidirectional"))
    )
    (net (code "64") (name "/TX3") (class "Default")
      (node (ref "J4") (pin "3") (pinfunction "3_3") (pintype "passive"))
      (node (ref "U3") (pin "8") (pinfunction "8/TX3/PWM_8") (pintype "bidirectional"))
      (node (ref "U9") (pin "TX") (pinfunction "TX_TX") (pintype "bidirectional"))
    )
    (net (code "65") (name "/TX_2") (class "Default")
      (node (ref "J5") (pin "4") (pinfunction "4_4") (pintype "passive"))
      (node (ref "U8") (pin "8") (pinfunction "CS_8") (pintype "bidirectional"))
    )
    (net (code "66") (name "/VUSB") (class "Default")
      (node (ref "J11") (pin "3") (pinfunction "3_3") (pintype "passive"))
      (node (ref "U3") (pin "VUSB") (pinfunction "VUSB_VUSB") (pintype "power_in"))
    )
    (net (code "67") (name "/WHITE_LED") (class "Default")
      (node (ref "D4") (pin "A") (pinfunction "A_A") (pintype "passive"))
      (node (ref "U3") (pin "23/A9") (pinfunction "23/A9/PWM_23/A9") (pintype "bidirectional"))
    )
    (net (code "68") (name "/YELLOW_LED") (class "Default")
      (node (ref "D3") (pin "A") (pinfunction "A_A") (pintype "passive"))
      (node (ref "U3") (pin "22/A8") (pinfunction "22/A8/PWM_22/A8") (pintype "bidirectional"))
    )
    (net (code "69") (name "Net-(D1-C)") (class "Default")
      (node (ref "D1") (pin "K") (pinfunction "C_K") (pintype "passive"))
      (node (ref "R1") (pin "P$2") (pinfunction "2_P$2") (pintype "passive"))
    )
    (net (code "70") (name "Net-(D2-C)") (class "Default")
      (node (ref "D2") (pin "K") (pinfunction "C_K") (pintype "passive"))
      (node (ref "R2") (pin "P$2") (pinfunction "2_P$2") (pintype "passive"))
    )
    (net (code "71") (name "Net-(D3-C)") (class "Default")
      (node (ref "D3") (pin "K") (pinfunction "C_K") (pintype "passive"))
      (node (ref "R3") (pin "P$2") (pinfunction "2_P$2") (pintype "passive"))
    )
    (net (code "72") (name "Net-(D4-C)") (class "Default")
      (node (ref "D4") (pin "K") (pinfunction "C_K") (pintype "passive"))
      (node (ref "R5") (pin "P$2") (pinfunction "2_P$2") (pintype "passive"))
    )
    (net (code "73") (name "Net-(D5-C)") (class "Default")
      (node (ref "D5") (pin "K") (pinfunction "C_K") (pintype "passive"))
      (node (ref "R4") (pin "P$2") (pinfunction "2_P$2") (pintype "passive"))
    )
    (net (code "74") (name "Net-(G0-P)") (class "Default")
      (node (ref "G0") (pin "1") (pinfunction "P_1") (pintype "passive"))
      (node (ref "U8") (pin "4") (pinfunction "G0_4") (pintype "bidirectional"))
    )
    (net (code "75") (name "Net-(G1-P)") (class "Default")
      (node (ref "G1") (pin "1") (pinfunction "P_1") (pintype "passive"))
      (node (ref "U8") (pin "10") (pinfunction "G1_10") (pintype "bidirectional"))
    )
    (net (code "76") (name "Net-(G2-P)") (class "Default")
      (node (ref "G2") (pin "1") (pinfunction "P_1") (pintype "passive"))
      (node (ref "U8") (pin "11") (pinfunction "G2_11") (pintype "bidirectional"))
    )
    (net (code "77") (name "Net-(G3-P)") (class "Default")
      (node (ref "G3") (pin "1") (pinfunction "P_1") (pintype "passive"))
      (node (ref "U8") (pin "12") (pinfunction "G3_12") (pintype "bidirectional"))
    )
    (net (code "78") (name "Net-(G4-P)") (class "Default")
      (node (ref "G4") (pin "1") (pinfunction "P_1") (pintype "passive"))
      (node (ref "U8") (pin "13") (pinfunction "G4_13") (pintype "bidirectional"))
    )
    (net (code "79") (name "Net-(G5-P)") (class "Default")
      (node (ref "G5") (pin "1") (pinfunction "P_1") (pintype "passive"))
      (node (ref "U8") (pin "14") (pinfunction "G5_14") (pintype "bidirectional"))
    )
    (net (code "80") (name "Net-(R10-2)") (class "Default")
      (node (ref "JP1") (pin "1") (pinfunction "1_1") (pintype "passive"))
      (node (ref "R10") (pin "P$2") (pinfunction "2_P$2") (pintype "passive"))
    )
    (net (code "81") (name "Net-(R11-2)") (class "Default")
      (node (ref "JP2") (pin "1") (pinfunction "1_1") (pintype "passive"))
      (node (ref "R11") (pin "P$2") (pinfunction "2_P$2") (pintype "passive"))
    )
    (net (code "82") (name "Net-(R12-2)") (class "Default")
      (node (ref "JP3") (pin "1") (pinfunction "1_1") (pintype "passive"))
      (node (ref "R12") (pin "P$2") (pinfunction "2_P$2") (pintype "passive"))
    )
    (net (code "83") (name "Net-(R13-2)") (class "Default")
      (node (ref "JP4") (pin "1") (pinfunction "1_1") (pintype "passive"))
      (node (ref "R13") (pin "P$2") (pinfunction "2_P$2") (pintype "passive"))
    )
    (net (code "84") (name "Net-(R14-2)") (class "Default")
      (node (ref "JP5") (pin "1") (pinfunction "1_1") (pintype "passive"))
      (node (ref "R14") (pin "P$2") (pinfunction "2_P$2") (pintype "passive"))
    )
    (net (code "85") (name "Net-(R15-2)") (class "Default")
      (node (ref "JP6") (pin "1") (pinfunction "1_1") (pintype "passive"))
      (node (ref "R15") (pin "P$2") (pinfunction "2_P$2") (pintype "passive"))
    )
    (net (code "86") (name "Net-(R16-2)") (class "Default")
      (node (ref "JP7") (pin "1") (pinfunction "1_1") (pintype "passive"))
      (node (ref "R16") (pin "P$2") (pinfunction "2_P$2") (pintype "passive"))
    )
    (net (code "87") (name "Net-(R17-2)") (class "Default")
      (node (ref "JP8") (pin "1") (pinfunction "1_1") (pintype "passive"))
      (node (ref "R17") (pin "P$2") (pinfunction "2_P$2") (pintype "passive"))
    )
    (net (code "88") (name "Net-(R18-2)") (class "Default")
      (node (ref "JP9") (pin "1") (pinfunction "1_1") (pintype "passive"))
      (node (ref "R18") (pin "P$2") (pinfunction "2_P$2") (pintype "passive"))
    )
    (net (code "89") (name "Net-(R19-2)") (class "Default")
      (node (ref "JP10") (pin "1") (pinfunction "1_1") (pintype "passive"))
      (node (ref "R19") (pin "P$2") (pinfunction "2_P$2") (pintype "passive"))
    )
    (net (code "90") (name "Net-(R20-2)") (class "Default")
      (node (ref "JP11") (pin "1") (pinfunction "1_1") (pintype "passive"))
      (node (ref "R20") (pin "P$2") (pinfunction "2_P$2") (pintype "passive"))
    )
    (net (code "91") (name "Net-(R21-2)") (class "Default")
      (node (ref "JP12") (pin "1") (pinfunction "1_1") (pintype "passive"))
      (node (ref "R21") (pin "P$2") (pinfunction "2_P$2") (pintype "passive"))
    )
    (net (code "92") (name "Net-(R22-2)") (class "Default")
      (node (ref "JP13") (pin "1") (pinfunction "1_1") (pintype "passive"))
      (node (ref "R22") (pin "P$2") (pinfunction "2_P$2") (pintype "passive"))
    )
    (net (code "93") (name "Net-(R23-2)") (class "Default")
      (node (ref "JP14") (pin "1") (pinfunction "1_1") (pintype "passive"))
      (node (ref "R23") (pin "P$2") (pinfunction "2_P$2") (pintype "passive"))
    )
    (net (code "94") (name "Net-(R24-2)") (class "Default")
      (node (ref "JP15") (pin "1") (pinfunction "1_1") (pintype "passive"))
      (node (ref "R24") (pin "P$2") (pinfunction "2_P$2") (pintype "passive"))
    )
    (net (code "95") (name "Net-(R25-2)") (class "Default")
      (node (ref "JP16") (pin "1") (pinfunction "1_1") (pintype "passive"))
      (node (ref "R25") (pin "P$2") (pinfunction "2_P$2") (pintype "passive"))
    )
    (net (code "96") (name "unconnected-(U1-PadGND)") (class "Default")
      (node (ref "U1") (pin "GND") (pinfunction "GND_GND") (pintype "input"))
    )
    (net (code "97") (name "unconnected-(U5-PadAUXCL)") (class "Default")
      (node (ref "U5") (pin "AUXCL") (pinfunction "AUXCL_AUXCL") (pintype "bidirectional"))
    )
    (net (code "98") (name "unconnected-(U5-PadAUXDA)") (class "Default")
      (node (ref "U5") (pin "AUXDA") (pinfunction "AUXDA_AUXDA") (pintype "bidirectional"))
    )
    (net (code "99") (name "unconnected-(U5-PadCS)") (class "Default")
      (node (ref "U5") (pin "CS") (pinfunction "CS_CS") (pintype "bidirectional"))
    )
    (net (code "100") (name "unconnected-(U5-PadVDDIO)") (class "Default")
      (node (ref "U5") (pin "VDDIO") (pinfunction "VDDIO_VDDIO") (pintype "bidirectional"))
    )
    (net (code "101") (name "unconnected-(U6-Pad3VO)") (class "Default")
      (node (ref "U6") (pin "3VO") (pinfunction "3VO_3VO") (pintype "bidirectional"))
    )
    (net (code "102") (name "unconnected-(U9-Pad3.3V)") (class "Default")
      (node (ref "U9") (pin "3.3V") (pinfunction "3.3V_3.3V") (pintype "bidirectional"))
    )
    (net (code "103") (name "unconnected-(U9-PadVBAT)") (class "Default")
      (node (ref "U9") (pin "VBAT") (pinfunction "VBAT_VBAT") (pintype "bidirectional"))
    )
  )
)
